# STMsch.net
KiCad netlist of a schematic drawn in EAGLE
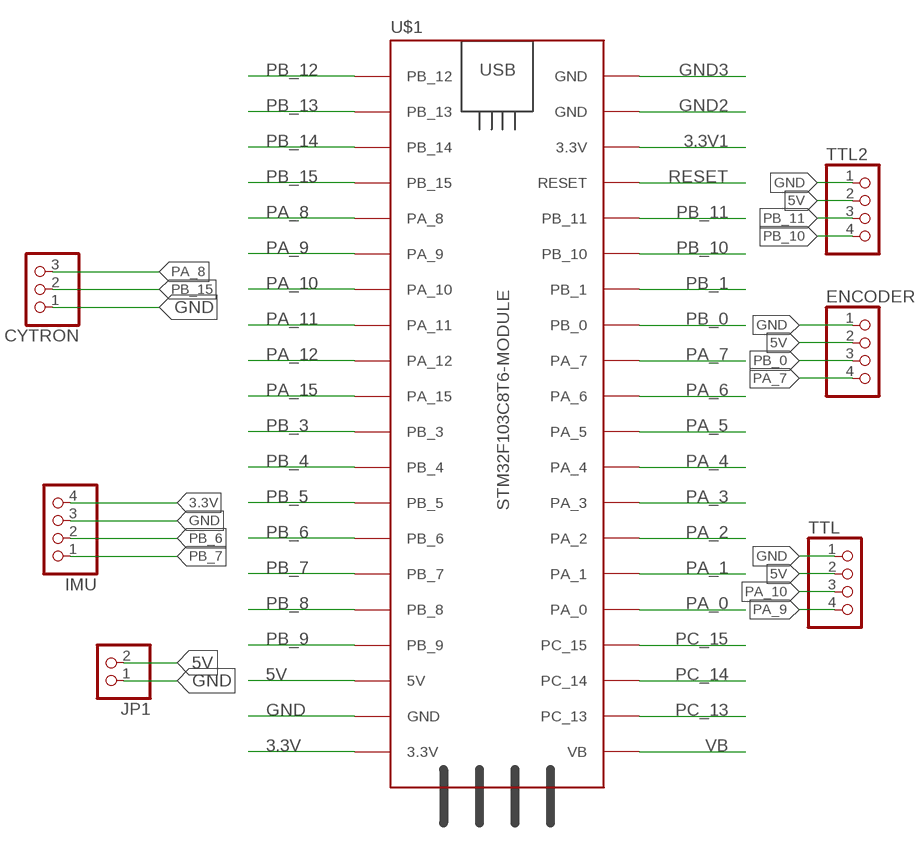
[diagram p0: schematic, sheet 1]

(export (version "E")
  (design (tool "Eeschema 10.0.6"))
  (components
    (comp (ref "CYTRON")
      (value "PINHD-3_DATA")
      (footprint "eagle-import:1X03_DATA")
      (libsource (lib "eagle-import") (part "PINHD-3_DATA"))
    )
    (comp (ref "ENCODER")
      (value "PINHD-4_DATA")
      (footprint "eagle-import:1X04_DATA")
      (libsource (lib "eagle-import") (part "PINHD-4_DATA"))
    )
    (comp (ref "IMU")
      (value "PINHD-1X4")
      (footprint "eagle-import:1X04")
      (libsource (lib "eagle-import") (part "PINHD-1X4"))
    )
    (comp (ref "JP1")
      (value "PINHD-2_DATA")
      (footprint "eagle-import:1X02_DATA")
      (libsource (lib "eagle-import") (part "PINHD-2_DATA"))
    )
    (comp (ref "TTL")
      (value "PINHD-4_DATA")
      (footprint "eagle-import:1X04_DATA")
      (libsource (lib "eagle-import") (part "PINHD-4_DATA"))
    )
    (comp (ref "TTL2")
      (value "PINHD-4_DATA")
      (footprint "eagle-import:1X04_DATA")
      (libsource (lib "eagle-import") (part "PINHD-4_DATA"))
    )
    (comp (ref "U$1")
      (value "STM32F103C8T6-MODULE")
      (footprint "eagle-import:STM32F103C8T6-MODULE")
      (libsource (lib "eagle-import") (part "STM32F103C8T6-MODULE"))
    )
  )
  (nets
    (net (code "1") (name "/3.3V1") (class "Default")
      (node (ref "U$1") (pin "3.3V_2") (pinfunction "3.3V_3.3V_2") (pintype "bidirectional"))
    )
    (net (code "2") (name "/GND2") (class "Default")
      (node (ref "U$1") (pin "GND_2") (pinfunction "GND_GND_2") (pintype "bidirectional"))
    )
    (net (code "3") (name "/GND3") (class "Default")
      (node (ref "U$1") (pin "GND_3") (pinfunction "GND_GND_3") (pintype "power_in"))
    )
    (net (code "4") (name "/PA_0") (class "Default")
      (node (ref "U$1") (pin "PA_0") (pinfunction "PA_0_PA_0") (pintype "bidirectional"))
    )
    (net (code "5") (name "/PA_1") (class "Default")
      (node (ref "U$1") (pin "PA_1") (pinfunction "PA_1_PA_1") (pintype "bidirectional"))
    )
    (net (code "6") (name "/PA_2") (class "Default")
      (node (ref "U$1") (pin "PA_2") (pinfunction "PA_2_PA_2") (pintype "bidirectional"))
    )
    (net (code "7") (name "/PA_3") (class "Default")
      (node (ref "U$1") (pin "PA_3") (pinfunction "PA_3_PA_3") (pintype "bidirectional"))
    )
    (net (code "8") (name "/PA_4") (class "Default")
      (node (ref "U$1") (pin "PA_4") (pinfunction "PA_4_PA_4") (pintype "bidirectional"))
    )
    (net (code "9") (name "/PA_5") (class "Default")
      (node (ref "U$1") (pin "PA_5") (pinfunction "PA_5_PA_5") (pintype "bidirectional"))
    )
    (net (code "10") (name "/PA_6") (class "Default")
      (node (ref "U$1") (pin "PA_6") (pinfunction "PA_6_PA_6") (pintype "bidirectional"))
    )
    (net (code "11") (name "/PA_11") (class "Default")
      (node (ref "U$1") (pin "PA_11") (pinfunction "PA_11_PA_11") (pintype "bidirectional"))
    )
    (net (code "12") (name "/PA_12") (class "Default")
      (node (ref "U$1") (pin "PA_12") (pinfunction "PA_12_PA_12") (pintype "bidirectional"))
    )
    (net (code "13") (name "/PA_15") (class "Default")
      (node (ref "U$1") (pin "PA_15") (pinfunction "PA_15_PA_15") (pintype "bidirectional"))
    )
    (net (code "14") (name "/PB_1") (class "Default")
      (node (ref "U$1") (pin "PB_1") (pinfunction "PB_1_PB_1") (pintype "bidirectional"))
    )
    (net (code "15") (name "/PB_3") (class "Default")
      (node (ref "U$1") (pin "PB_3") (pinfunction "PB_3_PB_3") (pintype "bidirectional"))
    )
    (net (code "16") (name "/PB_4") (class "Default")
      (node (ref "U$1") (pin "PB_4") (pinfunction "PB_4_PB_4") (pintype "bidirectional"))
    )
    (net (code "17") (name "/PB_5") (class "Default")
      (node (ref "U$1") (pin "PB_5") (pinfunction "PB_5_PB_5") (pintype "bidirectional"))
    )
    (net (code "18") (name "/PB_8") (class "Default")
      (node (ref "U$1") (pin "PB_8") (pinfunction "PB_8_PB_8") (pintype "bidirectional"))
    )
    (net (code "19") (name "/PB_9") (class "Default")
      (node (ref "U$1") (pin "PB_9") (pinfunction "PB_9_PB_9") (pintype "bidirectional"))
    )
    (net (code "20") (name "/PB_12") (class "Default")
      (node (ref "U$1") (pin "PB_12") (pinfunction "PB_12_PB_12") (pintype "bidirectional"))
    )
    (net (code "21") (name "/PB_13") (class "Default")
      (node (ref "U$1") (pin "PB_13") (pinfunction "PB_13_PB_13") (pintype "bidirectional"))
    )
    (net (code "22") (name "/PB_14") (class "Default")
      (node (ref "U$1") (pin "PB_14") (pinfunction "PB_14_PB_14") (pintype "bidirectional"))
    )
    (net (code "23") (name "/PC_13") (class "Default")
      (node (ref "U$1") (pin "PC_13") (pinfunction "PC_13_PC_13") (pintype "bidirectional"))
    )
    (net (code "24") (name "/PC_14") (class "Default")
      (node (ref "U$1") (pin "PC_14") (pinfunction "PC_14_PC_14") (pintype "bidirectional"))
    )
    (net (code "25") (name "/PC_15") (class "Default")
      (node (ref "U$1") (pin "PC_15") (pinfunction "PC_15_PC_15") (pintype "bidirectional"))
    )
    (net (code "26") (name "/RESET") (class "Default")
      (node (ref "U$1") (pin "RESET") (pinfunction "RESET_RESET") (pintype "bidirectional"))
    )
    (net (code "27") (name "/VB") (class "Default")
      (node (ref "U$1") (pin "VB") (pinfunction "VB_VB") (pintype "bidirectional"))
    )
    (net (code "28") (name "3.3V") (class "Default")
      (node (ref "IMU") (pin "4") (pinfunction "4_4") (pintype "passive"))
      (node (ref "U$1") (pin "3.3V_1") (pinfunction "3.3V_3.3V_1") (pintype "bidirectional"))
    )
    (net (code "29") (name "5V") (class "Default")
      (node (ref "ENCODER") (pin "2") (pinfunction "2_2") (pintype "passive"))
      (node (ref "JP1") (pin "2") (pinfunction "2_2") (pintype "passive"))
      (node (ref "TTL") (pin "2") (pinfunction "2_2") (pintype "passive"))
      (node (ref "TTL2") (pin "2") (pinfunction "2_2") (pintype "passive"))
      (node (ref "U$1") (pin "5V") (pinfunction "5V_5V") (pintype "bidirectional"))
    )
    (net (code "30") (name "GND") (class "Default")
      (node (ref "CYTRON") (pin "1") (pinfunction "1_1") (pintype "passive"))
      (node (ref "ENCODER") (pin "1") (pinfunction "1_1") (pintype "passive"))
      (node (ref "IMU") (pin "3") (pinfunction "3_3") (pintype "passive"))
      (node (ref "JP1") (pin "1") (pinfunction "1_1") (pintype "passive"))
      (node (ref "TTL") (pin "1") (pinfunction "1_1") (pintype "passive"))
      (node (ref "TTL2") (pin "1") (pinfunction "1_1") (pintype "passive"))
      (node (ref "U$1") (pin "GND_1") (pinfunction "GND_GND_1") (pintype "bidirectional"))
    )
    (net (code "31") (name "PA_7") (class "Default")
      (node (ref "ENCODER") (pin "4") (pinfunction "4_4") (pintype "passive"))
      (node (ref "U$1") (pin "PA_7") (pinfunction "PA_7_PA_7") (pintype "bidirectional"))
    )
    (net (code "32") (name "PA_8") (class "Default")
      (node (ref "CYTRON") (pin "3") (pinfunction "3_3") (pintype "passive"))
      (node (ref "U$1") (pin "PA_8") (pinfunction "PA_8_PA_8") (pintype "bidirectional"))
    )
    (net (code "33") (name "PA_9") (class "Default")
      (node (ref "TTL") (pin "4") (pinfunction "4_4") (pintype "passive"))
      (node (ref "U$1") (pin "PA_9") (pinfunction "PA_9_PA_9") (pintype "bidirectional"))
    )
    (net (code "34") (name "PA_10") (class "Default")
      (node (ref "TTL") (pin "3") (pinfunction "3_3") (pintype "passive"))
      (node (ref "U$1") (pin "PA_10") (pinfunction "PA_10_PA_10") (pintype "bidirectional"))
    )
    (net (code "35") (name "PB_0") (class "Default")
      (node (ref "ENCODER") (pin "3") (pinfunction "3_3") (pintype "passive"))
      (node (ref "U$1") (pin "PB_0") (pinfunction "PB_0_PB_0") (pintype "bidirectional"))
    )
    (net (code "36") (name "PB_6") (class "Default")
      (node (ref "IMU") (pin "2") (pinfunction "2_2") (pintype "passive"))
      (node (ref "U$1") (pin "PB_6") (pinfunction "PB_6_PB_6") (pintype "bidirectional"))
    )
    (net (code "37") (name "PB_7") (class "Default")
      (node (ref "IMU") (pin "1") (pinfunction "1_1") (pintype "passive"))
      (node (ref "U$1") (pin "PB_7") (pinfunction "PB_7_PB_7") (pintype "bidirectional"))
    )
    (net (code "38") (name "PB_10") (class "Default")
      (node (ref "TTL2") (pin "4") (pinfunction "4_4") (pintype "passive"))
      (node (ref "U$1") (pin "PB_10") (pinfunction "PB_10_PB_10") (pintype "bidirectional"))
    )
    (net (code "39") (name "PB_11") (class "Default")
      (node (ref "TTL2") (pin "3") (pinfunction "3_3") (pintype "passive"))
      (node (ref "U$1") (pin "PB_11") (pinfunction "PB_11_PB_11") (pintype "bidirectional"))
    )
    (net (code "40") (name "PB_15") (class "Default")
      (node (ref "CYTRON") (pin "2") (pinfunction "2_2") (pintype "passive"))
      (node (ref "U$1") (pin "PB_15") (pinfunction "PB_15_PB_15") (pintype "bidirectional"))
    )
  )
)
